# Flight_control_computer.net
KiCad netlist of a schematic drawn in EasyEDA
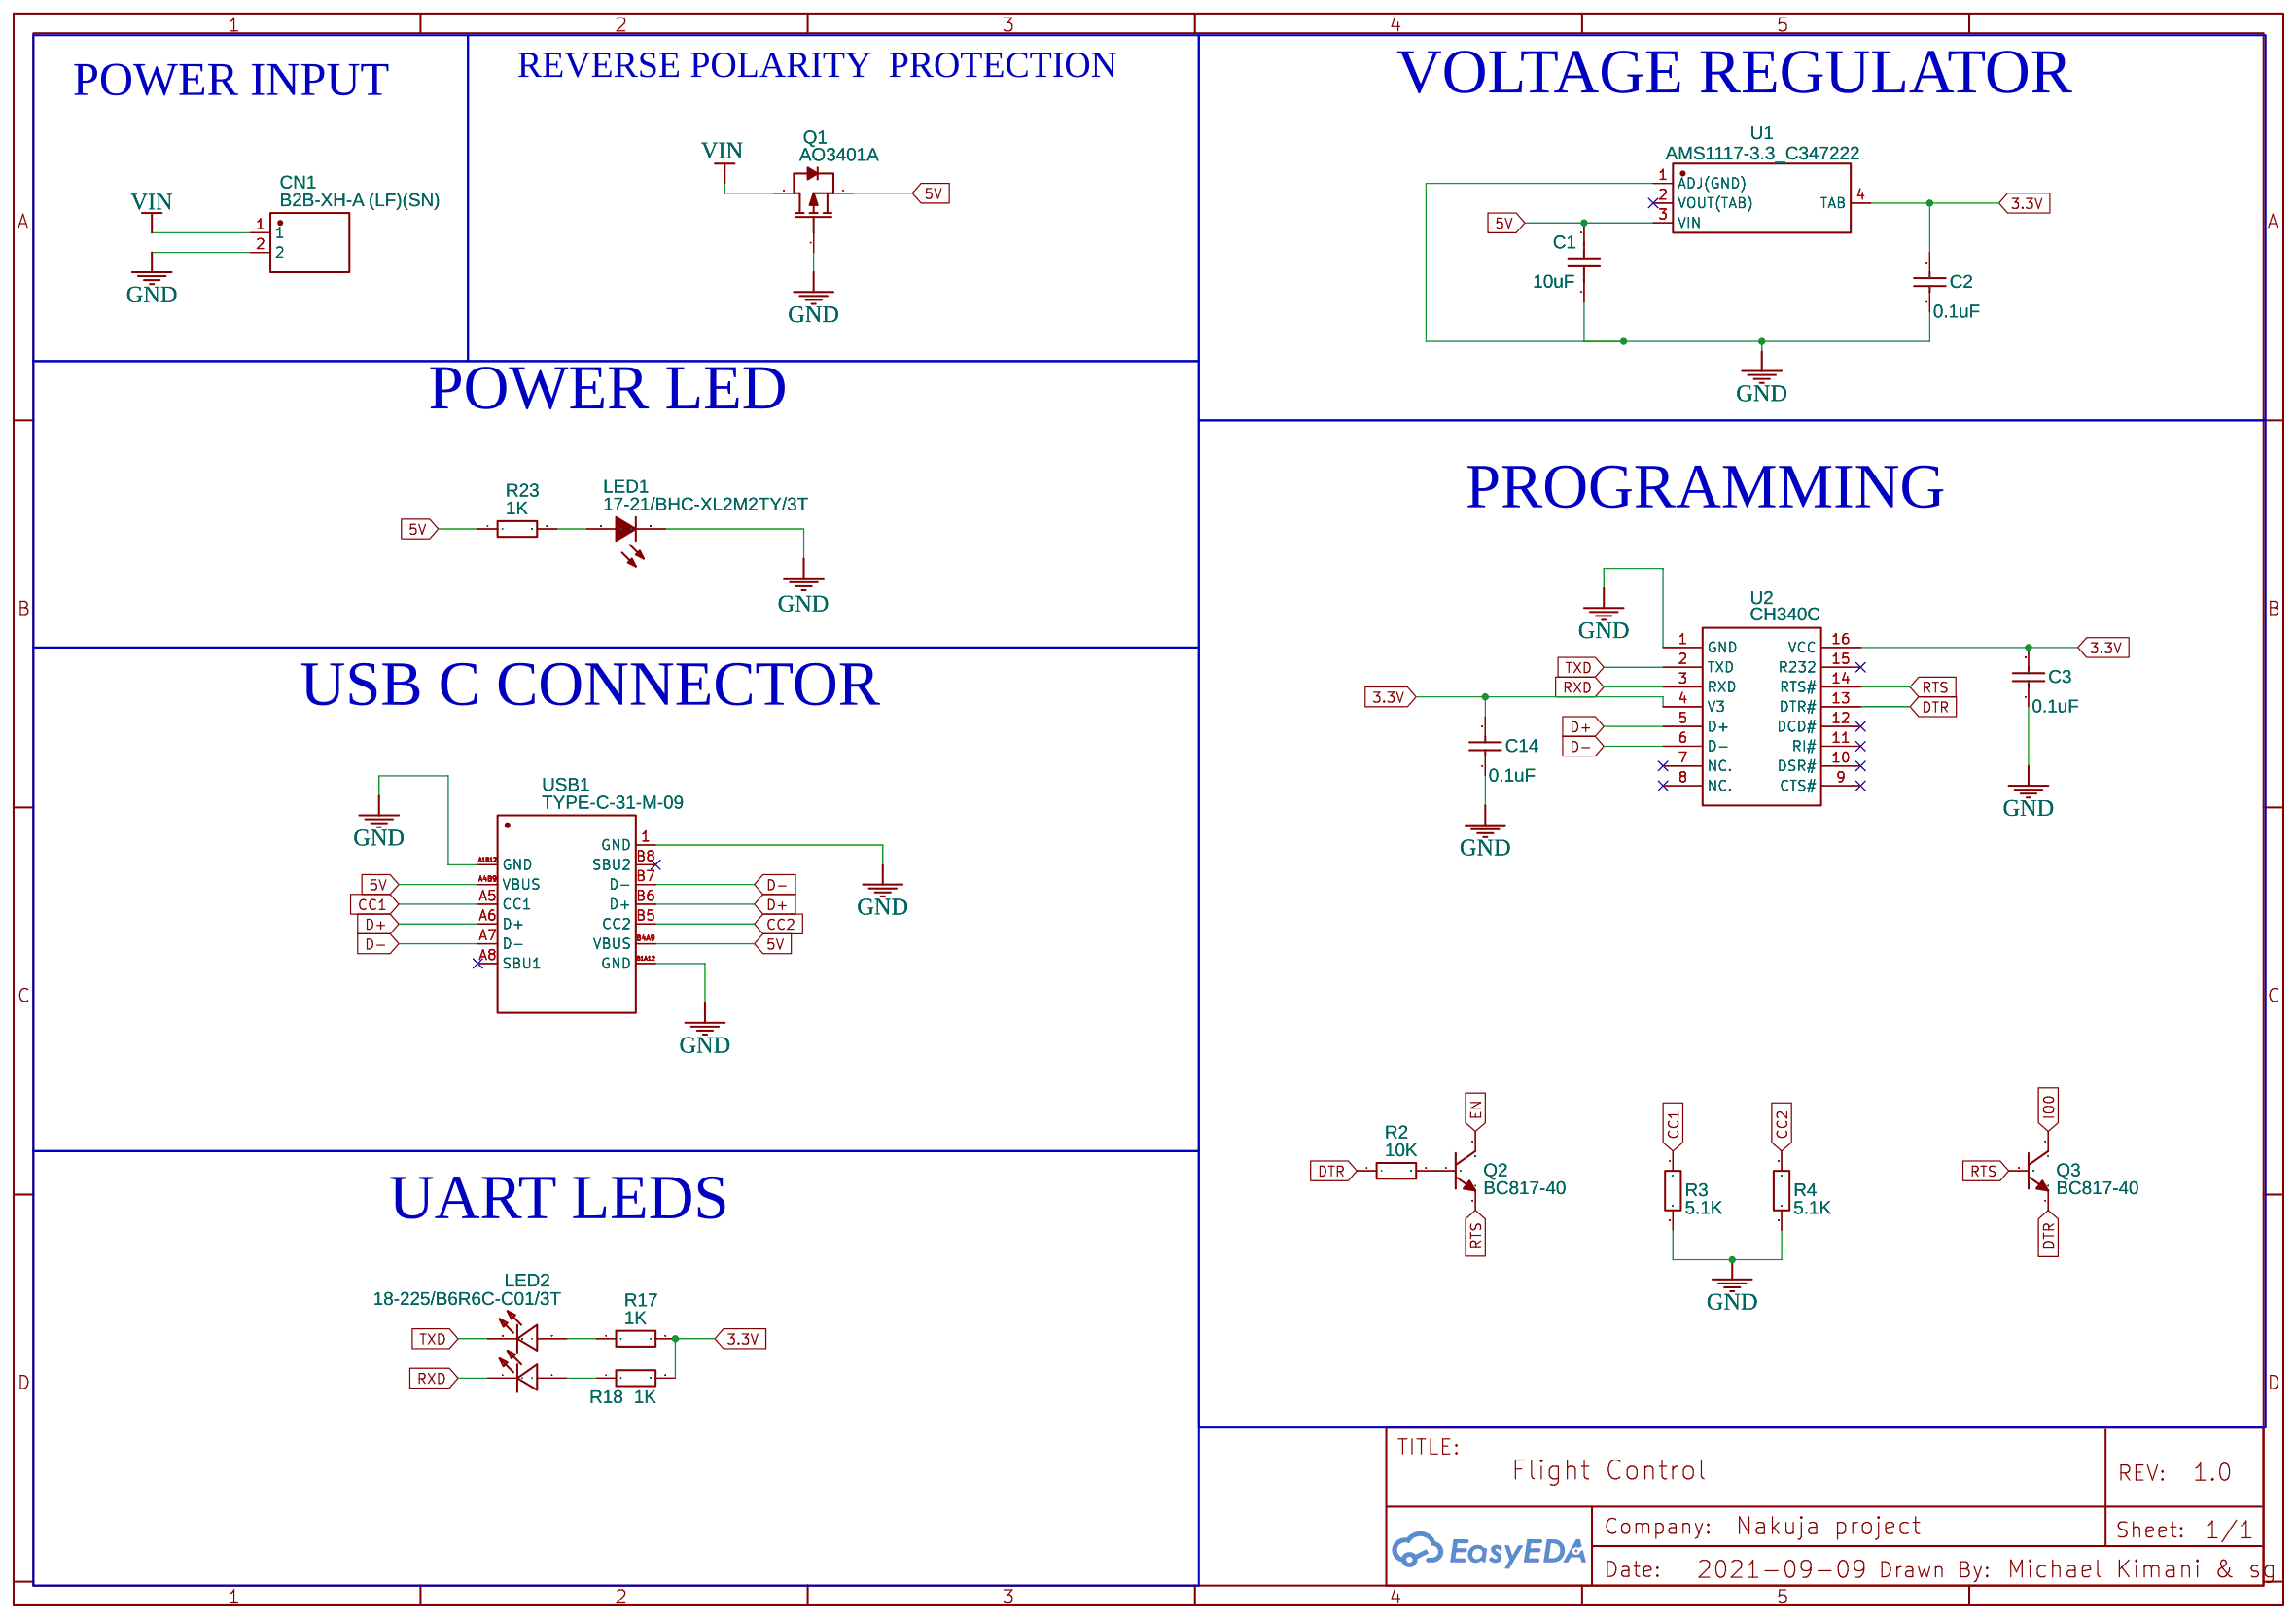
[diagram p0: power and programming]
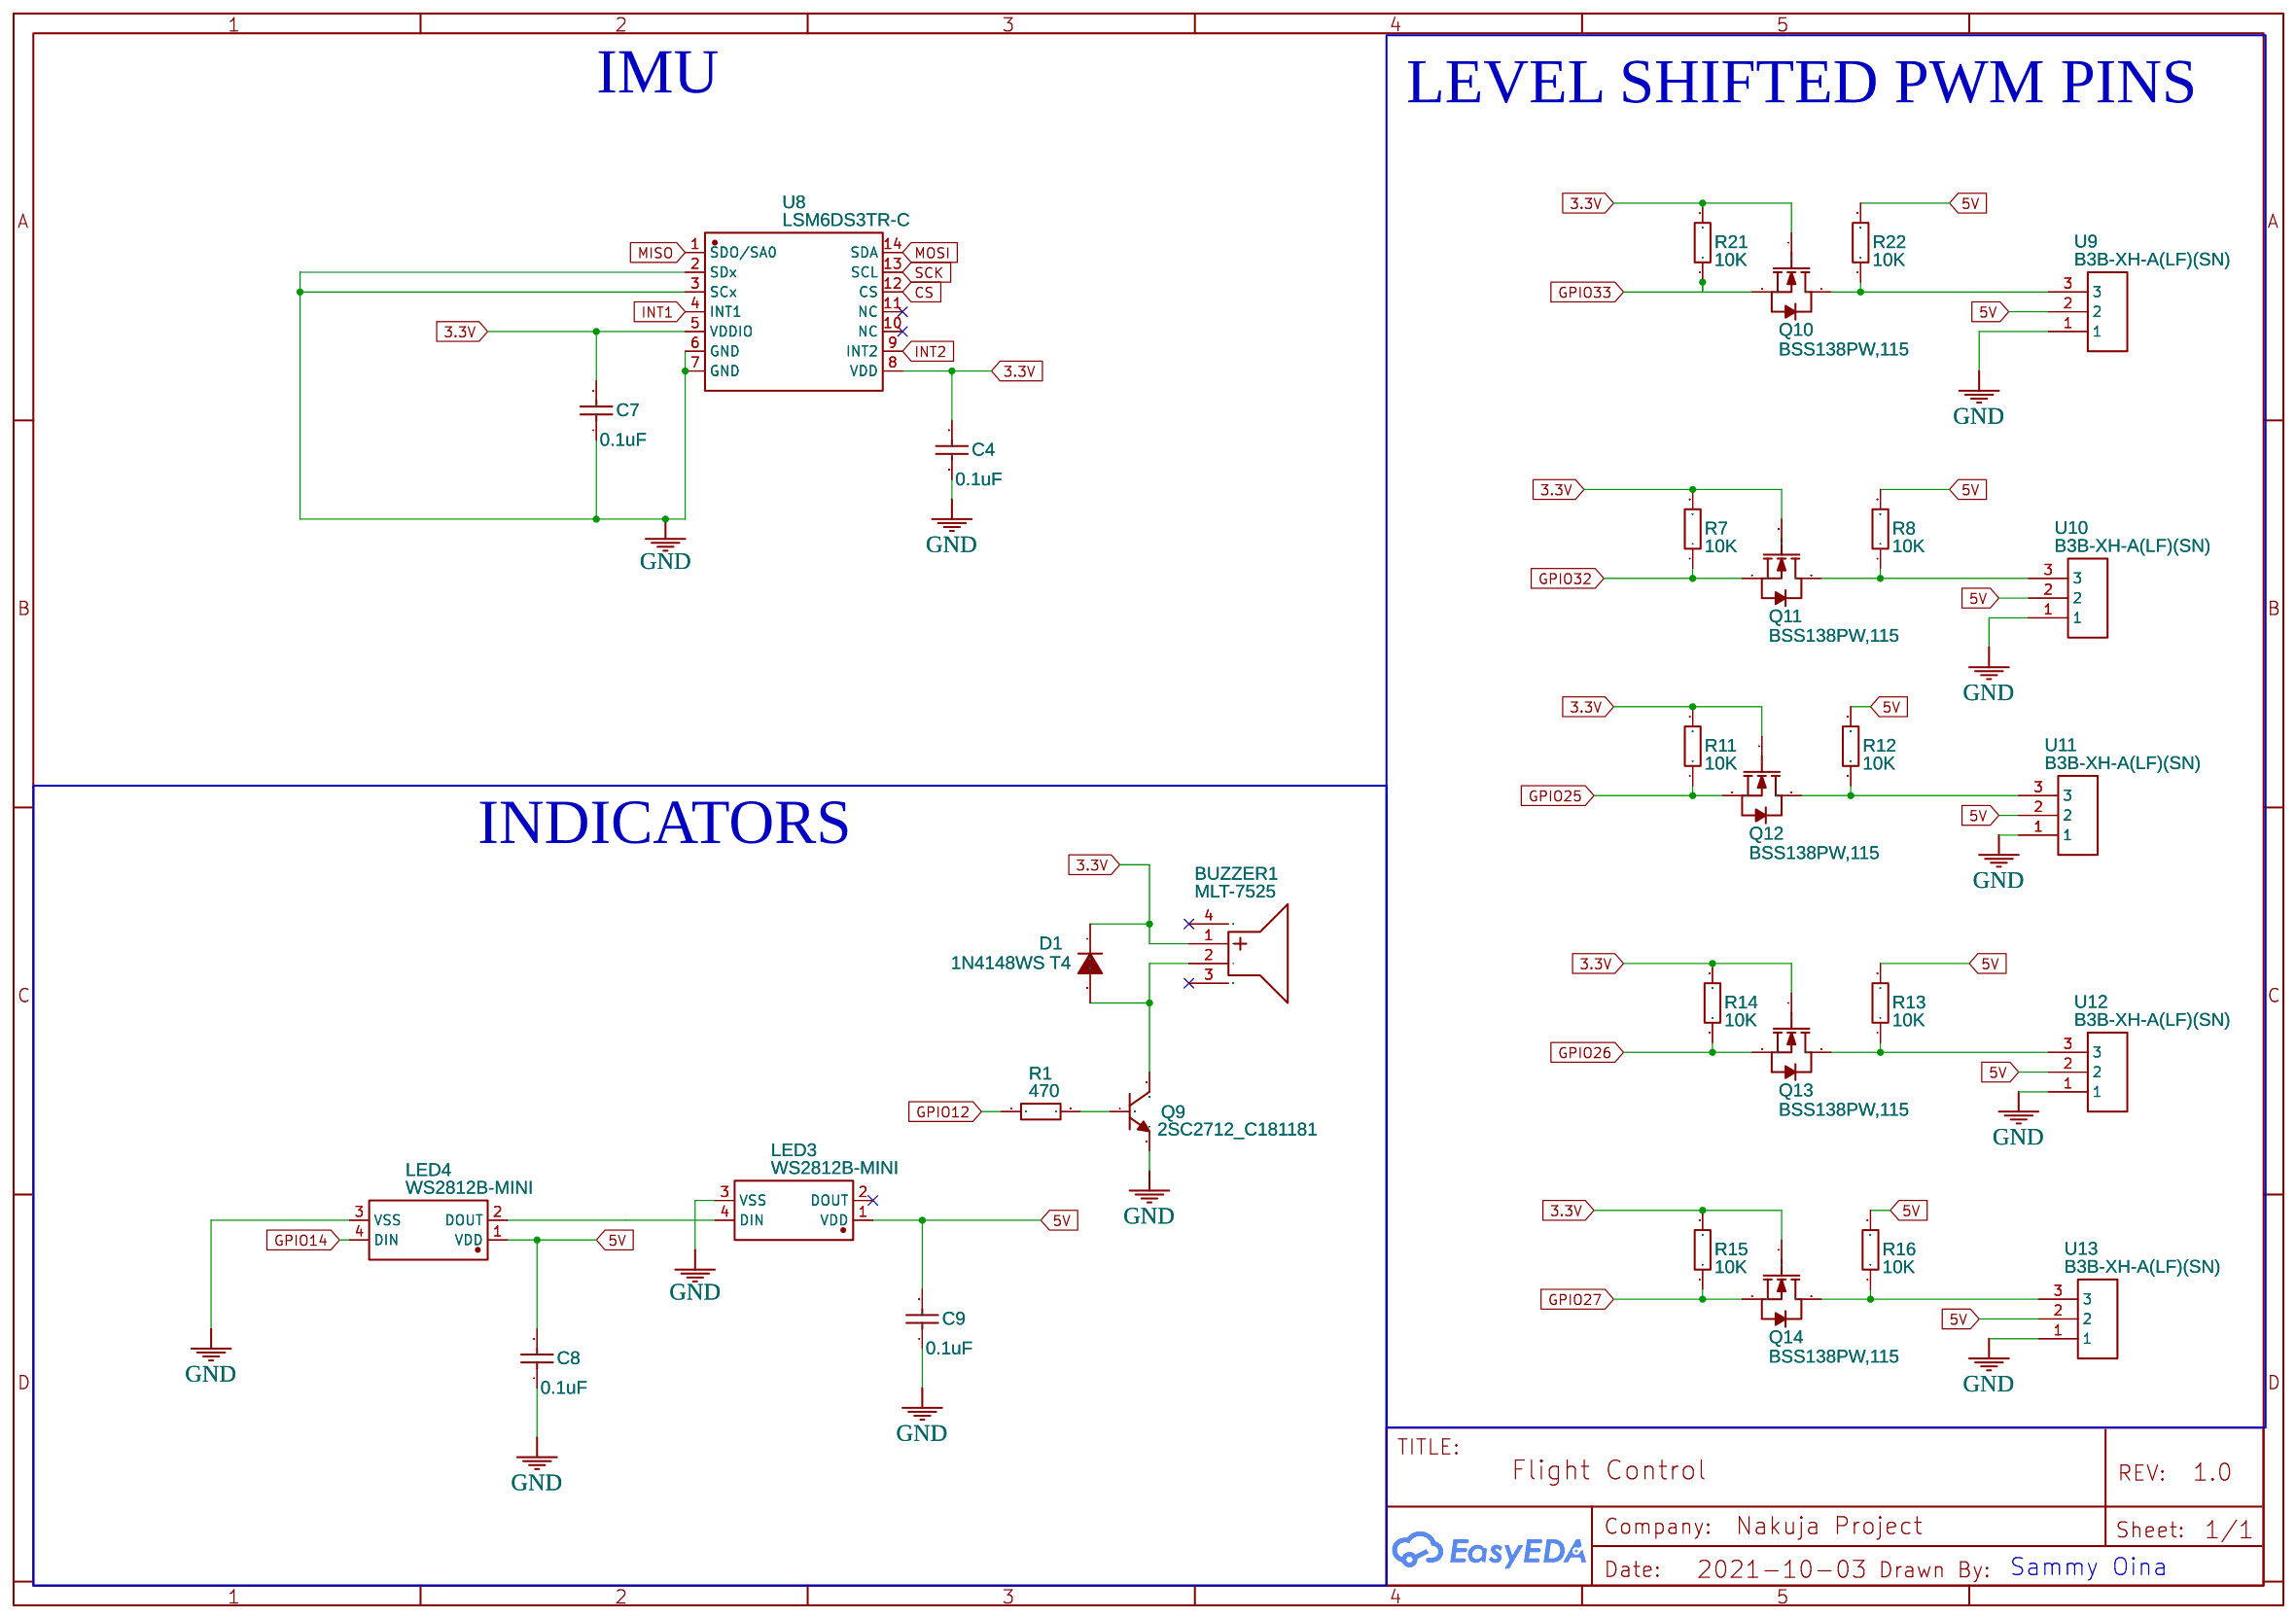
[diagram p1: indicators imu and pwmpins]
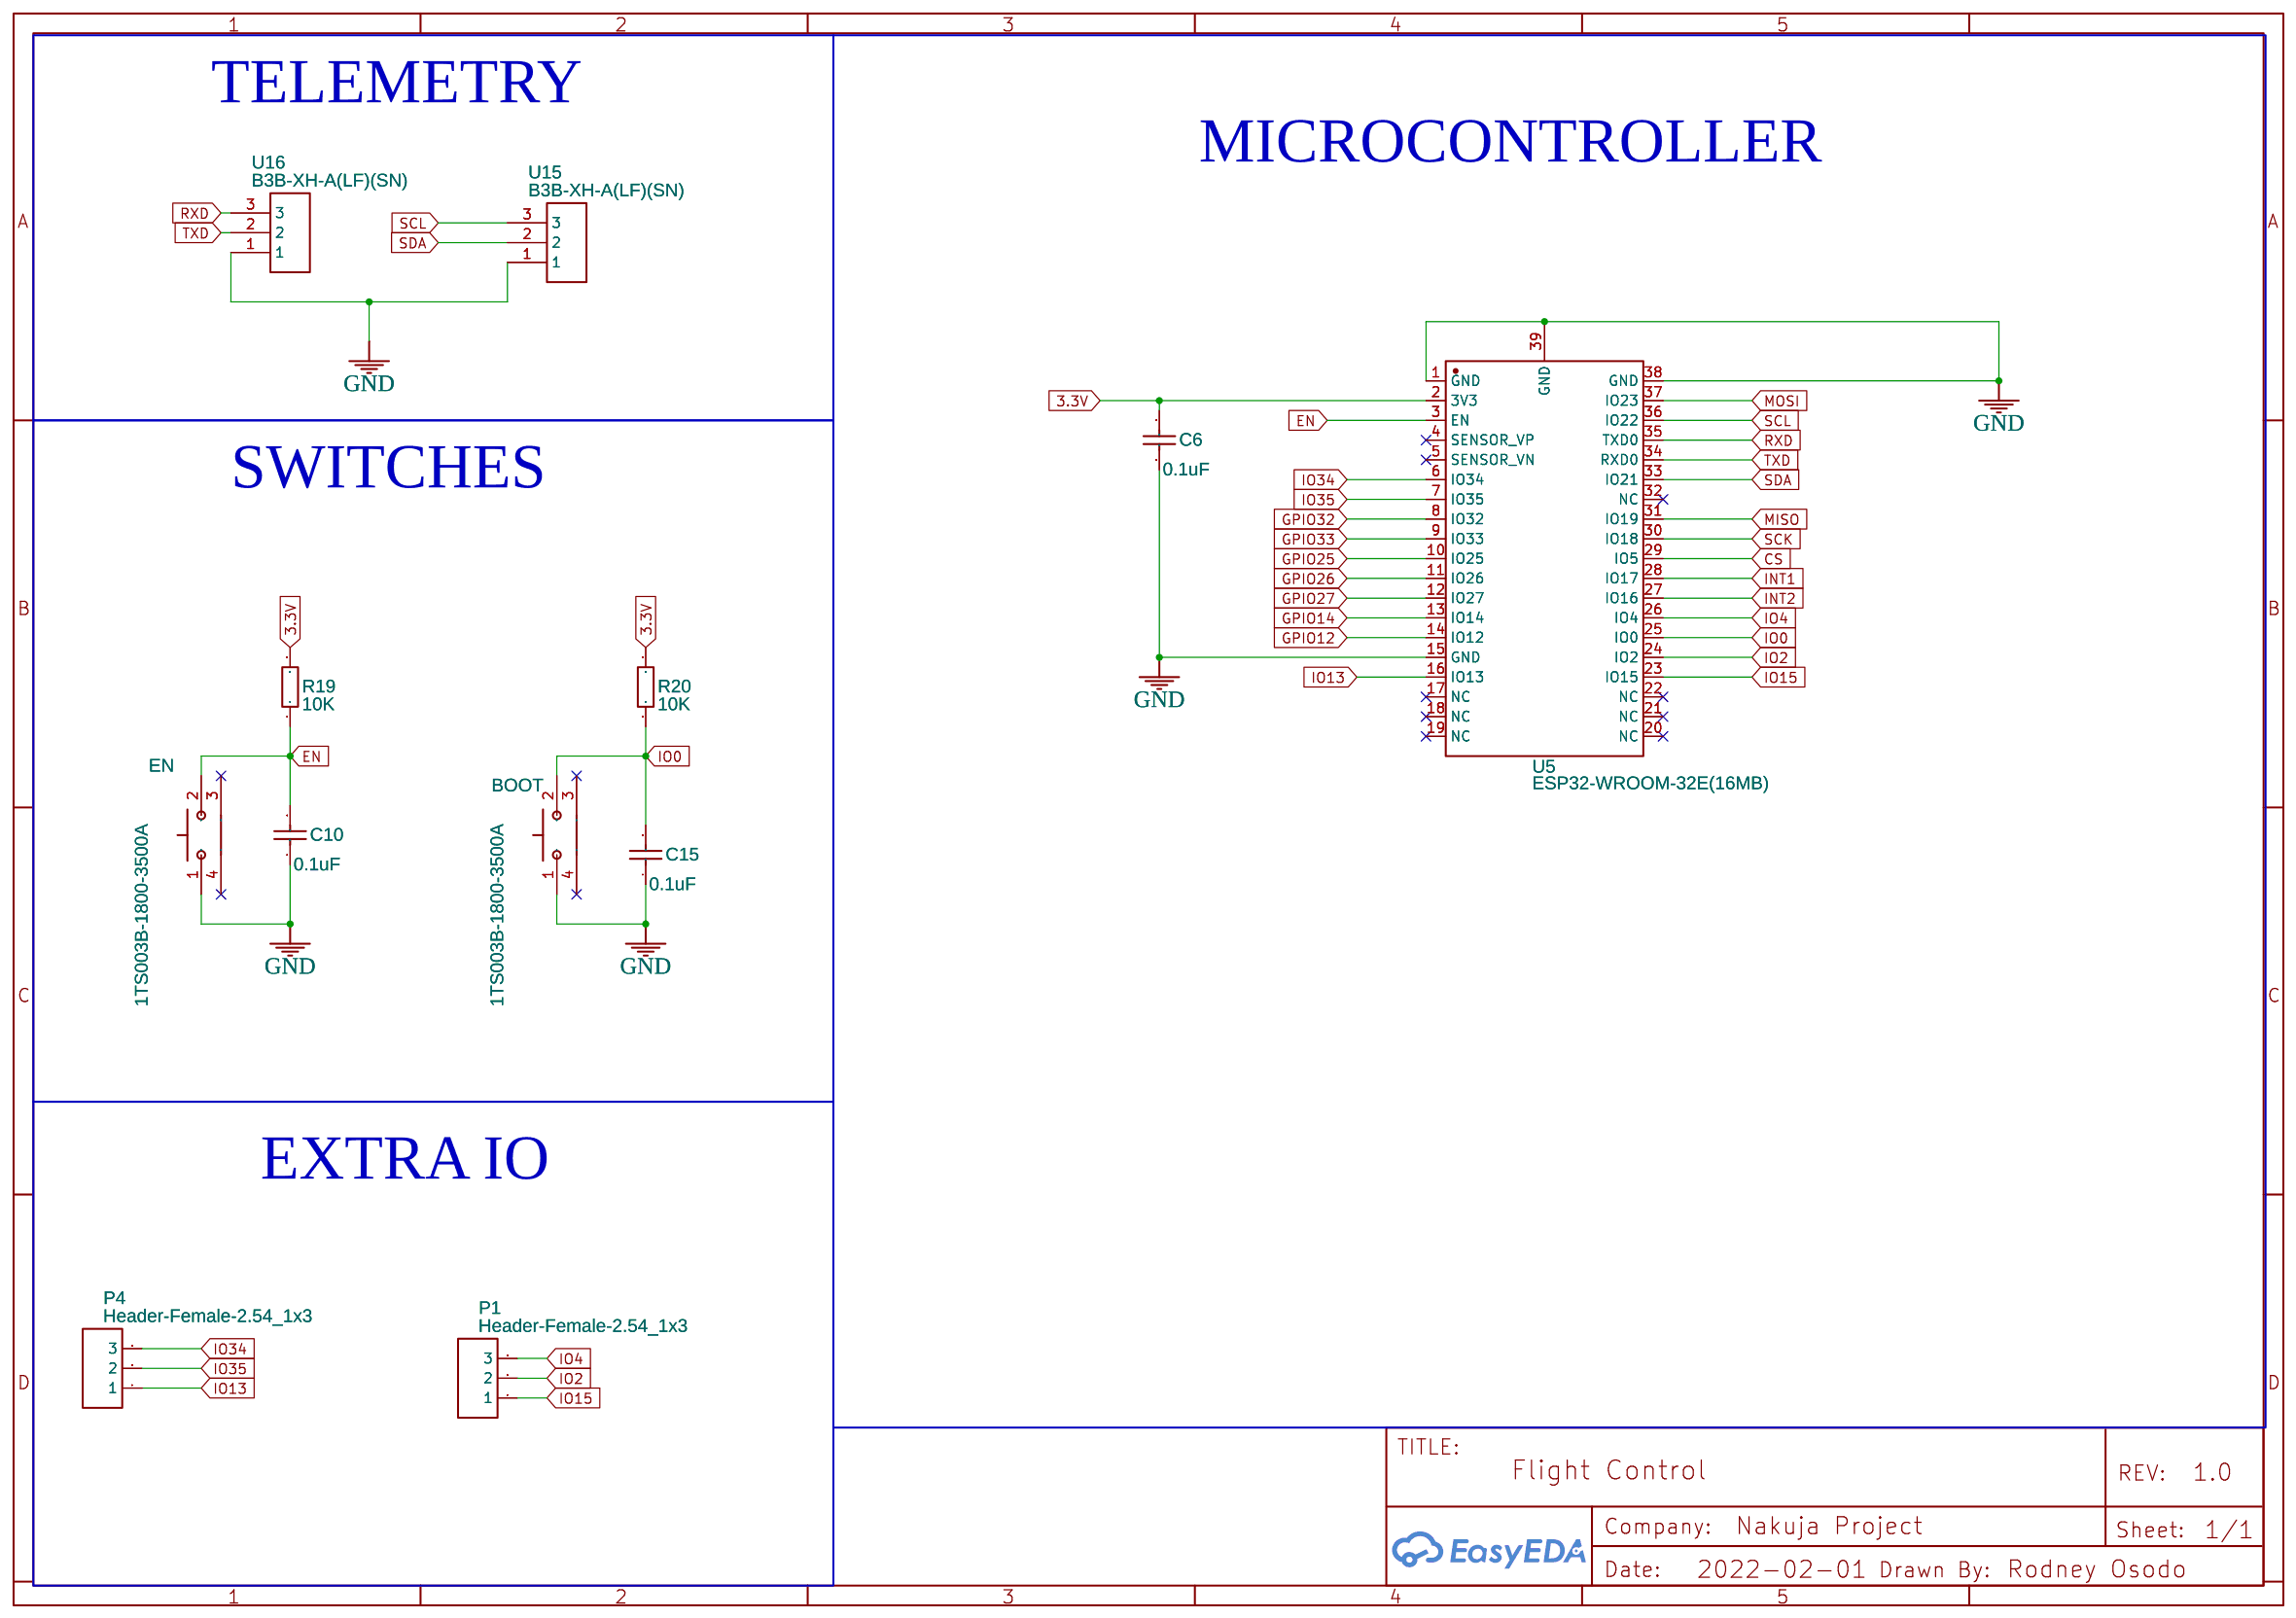
[diagram p2: microcontroller]

(export (version "E")
  (design (tool "Eeschema 10.0.6"))
  (components
    (comp (ref "C1")
      (value "10uF")
      (fields
        (field (name "BOM_Manufacturer Part") "CL05A106MQ8NUB8")
        (field (name "BOM_Supplier Part") "C307416")
      )
      (libsource (lib "") (part "CL05A106MQ8NUB8"))
    )
    (comp (ref "C2")
      (value "0.1uF")
      (fields
        (field (name "BOM_Manufacturer Part") "0603B104K250")
        (field (name "BOM_Supplier Part") "C83054")
      )
      (libsource (lib "") (part "0603B104K250"))
    )
    (comp (ref "C3")
      (value "0.1uF")
      (fields
        (field (name "BOM_Manufacturer Part") "0603B104K250")
        (field (name "BOM_Supplier Part") "C83054")
      )
      (libsource (lib "") (part "0603B104K250"))
    )
    (comp (ref "C14")
      (value "0.1uF")
      (fields
        (field (name "BOM_Manufacturer Part") "0603B104K250")
        (field (name "BOM_Supplier Part") "C83054")
      )
      (libsource (lib "") (part "0603B104K250"))
    )
    (comp (ref "CN1")
      (value "B2B-XH-A (LF)(SN)")
      (fields (field (name "BOM_Supplier Part") "C158012"))
      (libsource (lib "") (part "B2B-XH-A (LF)(SN)"))
    )
    (comp (ref "LED1")
      (value "17-21/BHC-XL2M2TY/3T")
      (fields (field (name "BOM_Supplier Part") "C72035"))
      (libsource (lib "") (part "17-21/BHC-XL2M2TY/3T"))
    )
    (comp (ref "LED2")
      (value "18-225/B6R6C-C01/3T")
      (fields (field (name "BOM_Supplier Part") "C282127"))
      (libsource (lib "") (part "18-225/B6R6C-C01/3T"))
    )
    (comp (ref "Q1")
      (value "AO3401A")
      (fields (field (name "BOM_Supplier Part") "C15127"))
      (libsource (lib "") (part "AO3401A"))
    )
    (comp (ref "Q2")
      (value "BC817-40")
      (fields (field (name "BOM_Supplier Part") "C181151"))
      (libsource (lib "") (part "BC817-40"))
    )
    (comp (ref "Q3")
      (value "BC817-40")
      (fields (field (name "BOM_Supplier Part") "C181151"))
      (libsource (lib "") (part "BC817-40"))
    )
    (comp (ref "R2")
      (value "10K")
      (fields
        (field (name "BOM_Manufacturer Part") "0402WGJ0103TCE")
        (field (name "BOM_Supplier Part") "C25531")
      )
      (libsource (lib "") (part "0402WGJ0103TCE"))
    )
    (comp (ref "R3")
      (value "5.1K")
      (fields
        (field (name "BOM_Manufacturer Part") "0402WGF5101TCE")
        (field (name "BOM_Supplier Part") "C25905")
      )
      (libsource (lib "") (part "0402WGF5101TCE"))
    )
    (comp (ref "R4")
      (value "5.1K")
      (fields
        (field (name "BOM_Manufacturer Part") "0402WGF5101TCE")
        (field (name "BOM_Supplier Part") "C25905")
      )
      (libsource (lib "") (part "0402WGF5101TCE"))
    )
    (comp (ref "R17")
      (value "1K")
      (fields
        (field (name "BOM_Manufacturer Part") "PTFR0805B1K00N9")
        (field (name "BOM_Supplier Part") "C328437")
      )
      (libsource (lib "") (part "PTFR0805B1K00N9"))
    )
    (comp (ref "R18")
      (value "1K")
      (fields
        (field (name "BOM_Manufacturer Part") "PTFR0805B1K00N9")
        (field (name "BOM_Supplier Part") "C328437")
      )
      (libsource (lib "") (part "PTFR0805B1K00N9"))
    )
    (comp (ref "R23")
      (value "1K")
      (fields
        (field (name "BOM_Manufacturer Part") "PTFR0805B1K00N9")
        (field (name "BOM_Supplier Part") "C328437")
      )
      (libsource (lib "") (part "PTFR0805B1K00N9"))
    )
    (comp (ref "U1")
      (value "AMS1117-3.3_C347222")
      (fields
        (field (name "BOM_Manufacturer Part") "AMS1117-3.3")
        (field (name "BOM_Supplier Part") "C347222")
      )
      (libsource (lib "") (part "AMS1117-3.3_C347222"))
    )
    (comp (ref "U2")
      (value "CH340C")
      (fields (field (name "BOM_Supplier Part") "C84681"))
      (libsource (lib "") (part "CH340C"))
    )
    (comp (ref "USB1")
      (value "TYPE-C-31-M-09")
      (fields (field (name "BOM_Supplier Part") "C2689967"))
      (libsource (lib "") (part "TYPE-C-31-M-09"))
    )
    (comp (ref "BUZZER1")
      (value "MLT-7525")
      (fields (field (name "BOM_Supplier Part") "C95299"))
      (libsource (lib "") (part "MLT-7525"))
    )
    (comp (ref "C4")
      (value "0.1uF")
      (fields
        (field (name "BOM_Manufacturer Part") "0603B104K250")
        (field (name "BOM_Supplier Part") "C83054")
      )
      (libsource (lib "") (part "0603B104K250"))
    )
    (comp (ref "C7")
      (value "0.1uF")
      (fields
        (field (name "BOM_Manufacturer Part") "0603B104K250")
        (field (name "BOM_Supplier Part") "C83054")
      )
      (libsource (lib "") (part "0603B104K250"))
    )
    (comp (ref "C8")
      (value "0.1uF")
      (fields
        (field (name "BOM_Manufacturer Part") "0603B104K250")
        (field (name "BOM_Supplier Part") "C83054")
      )
      (libsource (lib "") (part "0603B104K250"))
    )
    (comp (ref "C9")
      (value "0.1uF")
      (fields
        (field (name "BOM_Manufacturer Part") "0603B104K250")
        (field (name "BOM_Supplier Part") "C83054")
      )
      (libsource (lib "") (part "0603B104K250"))
    )
    (comp (ref "D1")
      (value "1N4148WS T4")
      (fields (field (name "BOM_Supplier Part") "C2128"))
      (libsource (lib "") (part "1N4148WS T4"))
    )
    (comp (ref "LED3")
      (value "WS2812B-MINI")
      (fields
        (field (name "BOM_Manufacturer Part") "WS2812B-Mini")
        (field (name "BOM_Supplier Part") "C527089")
      )
      (libsource (lib "") (part "WS2812B-MINI"))
    )
    (comp (ref "LED4")
      (value "WS2812B-MINI")
      (fields
        (field (name "BOM_Manufacturer Part") "WS2812B-Mini")
        (field (name "BOM_Supplier Part") "C527089")
      )
      (libsource (lib "") (part "WS2812B-MINI"))
    )
    (comp (ref "Q9")
      (value "2SC2712_C181181")
      (fields (field (name "BOM_Manufacturer Part") "2SC2712") (field (name "BOM_Supplier Part") "C181181"))
      (libsource (lib "") (part "2SC2712_C181181"))
    )
    (comp (ref "Q10")
      (value "BSS138PW,115")
      (fields (field (name "BOM_Supplier Part") "C193366"))
      (libsource (lib "") (part "BSS138PW,115"))
    )
    (comp (ref "Q11")
      (value "BSS138PW,115")
      (fields (field (name "BOM_Supplier Part") "C193366"))
      (libsource (lib "") (part "BSS138PW,115"))
    )
    (comp (ref "Q12")
      (value "BSS138PW,115")
      (fields (field (name "BOM_Supplier Part") "C193366"))
      (libsource (lib "") (part "BSS138PW,115"))
    )
    (comp (ref "Q13")
      (value "BSS138PW,115")
      (fields (field (name "BOM_Supplier Part") "C193366"))
      (libsource (lib "") (part "BSS138PW,115"))
    )
    (comp (ref "Q14")
      (value "BSS138PW,115")
      (fields (field (name "BOM_Supplier Part") "C193366"))
      (libsource (lib "") (part "BSS138PW,115"))
    )
    (comp (ref "R1")
      (value "470")
      (fields
        (field (name "BOM_Manufacturer Part") "0805W8F4700T5E")
        (field (name "BOM_Supplier Part") "C17710")
      )
      (libsource (lib "") (part "0805W8F4700T5E"))
    )
    (comp (ref "R7")
      (value "10K")
      (fields
        (field (name "BOM_Manufacturer Part") "0402WGJ0103TCE")
        (field (name "BOM_Supplier Part") "C25531")
      )
      (libsource (lib "") (part "0402WGJ0103TCE"))
    )
    (comp (ref "R8")
      (value "10K")
      (fields
        (field (name "BOM_Manufacturer Part") "0402WGJ0103TCE")
        (field (name "BOM_Supplier Part") "C25531")
      )
      (libsource (lib "") (part "0402WGJ0103TCE"))
    )
    (comp (ref "R11")
      (value "10K")
      (fields
        (field (name "BOM_Manufacturer Part") "0402WGJ0103TCE")
        (field (name "BOM_Supplier Part") "C25531")
      )
      (libsource (lib "") (part "0402WGJ0103TCE"))
    )
    (comp (ref "R12")
      (value "10K")
      (fields
        (field (name "BOM_Manufacturer Part") "0402WGJ0103TCE")
        (field (name "BOM_Supplier Part") "C25531")
      )
      (libsource (lib "") (part "0402WGJ0103TCE"))
    )
    (comp (ref "R13")
      (value "10K")
      (fields
        (field (name "BOM_Manufacturer Part") "0402WGJ0103TCE")
        (field (name "BOM_Supplier Part") "C25531")
      )
      (libsource (lib "") (part "0402WGJ0103TCE"))
    )
    (comp (ref "R14")
      (value "10K")
      (fields
        (field (name "BOM_Manufacturer Part") "0402WGJ0103TCE")
        (field (name "BOM_Supplier Part") "C25531")
      )
      (libsource (lib "") (part "0402WGJ0103TCE"))
    )
    (comp (ref "R15")
      (value "10K")
      (fields
        (field (name "BOM_Manufacturer Part") "0402WGJ0103TCE")
        (field (name "BOM_Supplier Part") "C25531")
      )
      (libsource (lib "") (part "0402WGJ0103TCE"))
    )
    (comp (ref "R16")
      (value "10K")
      (fields
        (field (name "BOM_Manufacturer Part") "0402WGJ0103TCE")
        (field (name "BOM_Supplier Part") "C25531")
      )
      (libsource (lib "") (part "0402WGJ0103TCE"))
    )
    (comp (ref "R21")
      (value "10K")
      (fields
        (field (name "BOM_Manufacturer Part") "0402WGJ0103TCE")
        (field (name "BOM_Supplier Part") "C25531")
      )
      (libsource (lib "") (part "0402WGJ0103TCE"))
    )
    (comp (ref "R22")
      (value "10K")
      (fields
        (field (name "BOM_Manufacturer Part") "0402WGJ0103TCE")
        (field (name "BOM_Supplier Part") "C25531")
      )
      (libsource (lib "") (part "0402WGJ0103TCE"))
    )
    (comp (ref "U8")
      (value "LSM6DS3TR-C")
      (fields (field (name "BOM_Supplier Part") "C967633"))
      (libsource (lib "") (part "LSM6DS3TR-C"))
    )
    (comp (ref "U9")
      (value "B3B-XH-A(LF)(SN)")
      (fields (field (name "BOM_Supplier Part") "C144394"))
      (libsource (lib "") (part "B3B-XH-A(LF)(SN)"))
    )
    (comp (ref "U10")
      (value "B3B-XH-A(LF)(SN)")
      (fields (field (name "BOM_Supplier Part") "C144394"))
      (libsource (lib "") (part "B3B-XH-A(LF)(SN)"))
    )
    (comp (ref "U11")
      (value "B3B-XH-A(LF)(SN)")
      (fields (field (name "BOM_Supplier Part") "C144394"))
      (libsource (lib "") (part "B3B-XH-A(LF)(SN)"))
    )
    (comp (ref "U12")
      (value "B3B-XH-A(LF)(SN)")
      (fields (field (name "BOM_Supplier Part") "C144394"))
      (libsource (lib "") (part "B3B-XH-A(LF)(SN)"))
    )
    (comp (ref "U13")
      (value "B3B-XH-A(LF)(SN)")
      (fields (field (name "BOM_Supplier Part") "C144394"))
      (libsource (lib "") (part "B3B-XH-A(LF)(SN)"))
    )
    (comp (ref "BOOT")
      (value "1TS003B-1800-3500A")
      (fields (field (name "BOM_Supplier Part") "C255809"))
      (libsource (lib "") (part "1TS003B-1800-3500A"))
    )
    (comp (ref "C6")
      (value "0.1uF")
      (fields
        (field (name "BOM_Manufacturer Part") "0603B104K250")
        (field (name "BOM_Supplier Part") "C83054")
      )
      (libsource (lib "") (part "0603B104K250"))
    )
    (comp (ref "C10")
      (value "0.1uF")
      (fields
        (field (name "BOM_Manufacturer Part") "0603B104K250")
        (field (name "BOM_Supplier Part") "C83054")
      )
      (libsource (lib "") (part "0603B104K250"))
    )
    (comp (ref "C15")
      (value "0.1uF")
      (fields
        (field (name "BOM_Manufacturer Part") "0603B104K250")
        (field (name "BOM_Supplier Part") "C83054")
      )
      (libsource (lib "") (part "0603B104K250"))
    )
    (comp (ref "EN")
      (value "1TS003B-1800-3500A")
      (fields (field (name "BOM_Supplier Part") "C255809"))
      (libsource (lib "") (part "1TS003B-1800-3500A_1"))
    )
    (comp (ref "P1")
      (value "Header-Female-2.54_1x3")
      (fields (field (name "BOM_Supplier Part") "C146243"))
      (libsource (lib "") (part "Header-Female-2.54_1x3"))
    )
    (comp (ref "P4")
      (value "Header-Female-2.54_1x3")
      (fields (field (name "BOM_Supplier Part") "C146243"))
      (libsource (lib "") (part "Header-Female-2.54_1x3"))
    )
    (comp (ref "R19")
      (value "10K")
      (fields
        (field (name "BOM_Manufacturer Part") "0402WGJ0103TCE")
        (field (name "BOM_Supplier Part") "C25531")
      )
      (libsource (lib "") (part "0402WGJ0103TCE"))
    )
    (comp (ref "R20")
      (value "10K")
      (fields
        (field (name "BOM_Manufacturer Part") "0402WGJ0103TCE")
        (field (name "BOM_Supplier Part") "C25531")
      )
      (libsource (lib "") (part "0402WGJ0103TCE"))
    )
    (comp (ref "U5")
      (value "ESP32-WROOM-32E(16MB)")
      (fields (field (name "BOM_Supplier Part") "C701343"))
      (libsource (lib "") (part "ESP32-WROOM-32E(16MB)"))
    )
    (comp (ref "U15")
      (value "B3B-XH-A(LF)(SN)")
      (fields (field (name "BOM_Supplier Part") "C144394"))
      (libsource (lib "") (part "B3B-XH-A(LF)(SN)"))
    )
    (comp (ref "U16")
      (value "B3B-XH-A(LF)(SN)")
      (fields (field (name "BOM_Supplier Part") "C144394"))
      (libsource (lib "") (part "B3B-XH-A(LF)(SN)"))
    )
  )
  (nets
    (net (code "1") (name "3.3V") (class "Default")
      (node (ref "BUZZER1") (pin "1") (pinfunction "+_1") (pintype "unspecified"))
      (node (ref "C14") (pin "2") (pinfunction "2_2") (pintype "input"))
      (node (ref "C2") (pin "2") (pinfunction "2_2") (pintype "input"))
      (node (ref "C3") (pin "2") (pinfunction "2_2") (pintype "input"))
      (node (ref "C4") (pin "2") (pinfunction "2_2") (pintype "input"))
      (node (ref "C6") (pin "2") (pinfunction "2_2") (pintype "input"))
      (node (ref "C7") (pin "2") (pinfunction "2_2") (pintype "input"))
      (node (ref "D1") (pin "1") (pinfunction "K_1") (pintype "unspecified"))
      (node (ref "Q10") (pin "1") (pinfunction "G_1") (pintype "unspecified"))
      (node (ref "Q11") (pin "1") (pinfunction "G_1") (pintype "unspecified"))
      (node (ref "Q12") (pin "1") (pinfunction "G_1") (pintype "unspecified"))
      (node (ref "Q13") (pin "1") (pinfunction "G_1") (pintype "unspecified"))
      (node (ref "Q14") (pin "1") (pinfunction "G_1") (pintype "unspecified"))
      (node (ref "R11") (pin "2") (pinfunction "2_2") (pintype "input"))
      (node (ref "R14") (pin "2") (pinfunction "2_2") (pintype "input"))
      (node (ref "R15") (pin "2") (pinfunction "2_2") (pintype "input"))
      (node (ref "R17") (pin "2") (pinfunction "2_2") (pintype "unspecified"))
      (node (ref "R18") (pin "2") (pinfunction "2_2") (pintype "unspecified"))
      (node (ref "R19") (pin "2") (pinfunction "2_2") (pintype "input"))
      (node (ref "R20") (pin "2") (pinfunction "2_2") (pintype "input"))
      (node (ref "R21") (pin "2") (pinfunction "2_2") (pintype "input"))
      (node (ref "R7") (pin "2") (pinfunction "2_2") (pintype "input"))
      (node (ref "U1") (pin "4") (pinfunction "TAB_4") (pintype "unspecified"))
      (node (ref "U2") (pin "16") (pinfunction "VCC_16") (pintype "unspecified"))
      (node (ref "U2") (pin "4") (pinfunction "V3_4") (pintype "unspecified"))
      (node (ref "U5") (pin "2") (pinfunction "3V3_2") (pintype "unspecified"))
      (node (ref "U8") (pin "5") (pinfunction "VDDIO_5") (pintype "unspecified"))
      (node (ref "U8") (pin "8") (pinfunction "VDD_8") (pintype "unspecified"))
    )
    (net (code "2") (name "5V") (class "Default")
      (node (ref "C1") (pin "2") (pinfunction "2_2") (pintype "unspecified"))
      (node (ref "C8") (pin "2") (pinfunction "2_2") (pintype "input"))
      (node (ref "C9") (pin "2") (pinfunction "2_2") (pintype "input"))
      (node (ref "LED3") (pin "1") (pinfunction "VDD_1") (pintype "unspecified"))
      (node (ref "LED4") (pin "1") (pinfunction "VDD_1") (pintype "unspecified"))
      (node (ref "Q1") (pin "2") (pinfunction "S_2") (pintype "unspecified"))
      (node (ref "R12") (pin "2") (pinfunction "2_2") (pintype "input"))
      (node (ref "R13") (pin "2") (pinfunction "2_2") (pintype "input"))
      (node (ref "R16") (pin "2") (pinfunction "2_2") (pintype "input"))
      (node (ref "R22") (pin "2") (pinfunction "2_2") (pintype "input"))
      (node (ref "R23") (pin "1") (pinfunction "1_1") (pintype "unspecified"))
      (node (ref "R8") (pin "2") (pinfunction "2_2") (pintype "input"))
      (node (ref "U1") (pin "3") (pinfunction "VIN_3") (pintype "unspecified"))
      (node (ref "U10") (pin "2") (pinfunction "2_2") (pintype "unspecified"))
      (node (ref "U11") (pin "2") (pinfunction "2_2") (pintype "unspecified"))
      (node (ref "U12") (pin "2") (pinfunction "2_2") (pintype "unspecified"))
      (node (ref "U13") (pin "2") (pinfunction "2_2") (pintype "unspecified"))
      (node (ref "U9") (pin "2") (pinfunction "2_2") (pintype "unspecified"))
      (node (ref "USB1") (pin "A4B9") (pinfunction "VBUS_A4B9") (pintype "unspecified"))
      (node (ref "USB1") (pin "B4A9") (pinfunction "VBUS_B4A9") (pintype "unspecified"))
    )
    (net (code "3") (name "CC1") (class "Default")
      (node (ref "R3") (pin "1") (pinfunction "1_1") (pintype "input"))
      (node (ref "USB1") (pin "A5") (pinfunction "CC1_A5") (pintype "unspecified"))
    )
    (net (code "4") (name "CC2") (class "Default")
      (node (ref "R4") (pin "1") (pinfunction "1_1") (pintype "input"))
      (node (ref "USB1") (pin "B5") (pinfunction "CC2_B5") (pintype "unspecified"))
    )
    (net (code "5") (name "CS") (class "Default")
      (node (ref "U5") (pin "29") (pinfunction "IO5_29") (pintype "unspecified"))
      (node (ref "U8") (pin "12") (pinfunction "CS_12") (pintype "unspecified"))
    )
    (net (code "6") (name "D+") (class "Default")
      (node (ref "U2") (pin "5") (pinfunction "D+_5") (pintype "unspecified"))
      (node (ref "USB1") (pin "A6") (pinfunction "D+_A6") (pintype "unspecified"))
      (node (ref "USB1") (pin "B6") (pinfunction "D+_B6") (pintype "unspecified"))
    )
    (net (code "7") (name "D-") (class "Default")
      (node (ref "U2") (pin "6") (pinfunction "D-_6") (pintype "unspecified"))
      (node (ref "USB1") (pin "A7") (pinfunction "D-_A7") (pintype "unspecified"))
      (node (ref "USB1") (pin "B7") (pinfunction "D-_B7") (pintype "unspecified"))
    )
    (net (code "8") (name "DTR") (class "Default")
      (node (ref "Q3") (pin "2") (pinfunction "2_2") (pintype "input"))
      (node (ref "R2") (pin "1") (pinfunction "1_1") (pintype "input"))
      (node (ref "U2") (pin "13") (pinfunction "DTR#_13") (pintype "unspecified"))
    )
    (net (code "9") (name "EN") (class "Default")
      (node (ref "C10") (pin "2") (pinfunction "2_2") (pintype "input"))
      (node (ref "EN") (pin "2") (pinfunction "2_2") (pintype "unspecified"))
      (node (ref "Q2") (pin "3") (pinfunction "3_3") (pintype "input"))
      (node (ref "R19") (pin "1") (pinfunction "1_1") (pintype "input"))
      (node (ref "U5") (pin "3") (pinfunction "EN_3") (pintype "unspecified"))
    )
    (net (code "10") (name "GND") (class "Default")
      (node (ref "BOOT") (pin "1") (pinfunction "1_1") (pintype "unspecified"))
      (node (ref "C1") (pin "1") (pinfunction "1_1") (pintype "unspecified"))
      (node (ref "C10") (pin "1") (pinfunction "1_1") (pintype "input"))
      (node (ref "C14") (pin "1") (pinfunction "1_1") (pintype "input"))
      (node (ref "C15") (pin "1") (pinfunction "1_1") (pintype "input"))
      (node (ref "C2") (pin "1") (pinfunction "1_1") (pintype "input"))
      (node (ref "C3") (pin "1") (pinfunction "1_1") (pintype "input"))
      (node (ref "C4") (pin "1") (pinfunction "1_1") (pintype "input"))
      (node (ref "C6") (pin "1") (pinfunction "1_1") (pintype "input"))
      (node (ref "C7") (pin "1") (pinfunction "1_1") (pintype "input"))
      (node (ref "C8") (pin "1") (pinfunction "1_1") (pintype "input"))
      (node (ref "C9") (pin "1") (pinfunction "1_1") (pintype "input"))
      (node (ref "CN1") (pin "2") (pinfunction "2_2") (pintype "unspecified"))
      (node (ref "EN") (pin "1") (pinfunction "1_1") (pintype "unspecified"))
      (node (ref "LED1") (pin "1") (pinfunction "-_1") (pintype "input"))
      (node (ref "LED3") (pin "3") (pinfunction "VSS_3") (pintype "unspecified"))
      (node (ref "LED4") (pin "3") (pinfunction "VSS_3") (pintype "unspecified"))
      (node (ref "Q1") (pin "1") (pinfunction "G_1") (pintype "unspecified"))
      (node (ref "Q9") (pin "2") (pinfunction "E_2") (pintype "input"))
      (node (ref "R3") (pin "2") (pinfunction "2_2") (pintype "input"))
      (node (ref "R4") (pin "2") (pinfunction "2_2") (pintype "input"))
      (node (ref "U1") (pin "1") (pinfunction "ADJ(GND)_1") (pintype "unspecified"))
      (node (ref "U10") (pin "1") (pinfunction "1_1") (pintype "unspecified"))
      (node (ref "U11") (pin "1") (pinfunction "1_1") (pintype "unspecified"))
      (node (ref "U12") (pin "1") (pinfunction "1_1") (pintype "unspecified"))
      (node (ref "U13") (pin "1") (pinfunction "1_1") (pintype "unspecified"))
      (node (ref "U15") (pin "1") (pinfunction "1_1") (pintype "unspecified"))
      (node (ref "U16") (pin "1") (pinfunction "1_1") (pintype "unspecified"))
      (node (ref "U2") (pin "1") (pinfunction "GND_1") (pintype "unspecified"))
      (node (ref "U5") (pin "1") (pinfunction "GND_1") (pintype "unspecified"))
      (node (ref "U5") (pin "15") (pinfunction "GND_15") (pintype "unspecified"))
      (node (ref "U5") (pin "38") (pinfunction "GND_38") (pintype "unspecified"))
      (node (ref "U5") (pin "39") (pinfunction "GND_39") (pintype "unspecified"))
      (node (ref "U8") (pin "2") (pinfunction "SDx_2") (pintype "unspecified"))
      (node (ref "U8") (pin "3") (pinfunction "SCx_3") (pintype "unspecified"))
      (node (ref "U8") (pin "6") (pinfunction "GND_6") (pintype "unspecified"))
      (node (ref "U8") (pin "7") (pinfunction "GND_7") (pintype "unspecified"))
      (node (ref "U9") (pin "1") (pinfunction "1_1") (pintype "unspecified"))
      (node (ref "USB1") (pin "1") (pinfunction "GND_1") (pintype "unspecified"))
      (node (ref "USB1") (pin "A1B12") (pinfunction "GND_A1B12") (pintype "unspecified"))
      (node (ref "USB1") (pin "B1A12") (pinfunction "GND_B1A12") (pintype "unspecified"))
    )
    (net (code "11") (name "GPIO12") (class "Default")
      (node (ref "R1") (pin "1") (pinfunction "1_1") (pintype "input"))
      (node (ref "U5") (pin "14") (pinfunction "IO12_14") (pintype "unspecified"))
    )
    (net (code "12") (name "GPIO14") (class "Default")
      (node (ref "LED4") (pin "4") (pinfunction "DIN_4") (pintype "unspecified"))
      (node (ref "U5") (pin "13") (pinfunction "IO14_13") (pintype "unspecified"))
    )
    (net (code "13") (name "GPIO25") (class "Default")
      (node (ref "Q12") (pin "2") (pinfunction "S_2") (pintype "unspecified"))
      (node (ref "R11") (pin "1") (pinfunction "1_1") (pintype "input"))
      (node (ref "U5") (pin "10") (pinfunction "IO25_10") (pintype "unspecified"))
    )
    (net (code "14") (name "GPIO26") (class "Default")
      (node (ref "Q13") (pin "2") (pinfunction "S_2") (pintype "unspecified"))
      (node (ref "R14") (pin "1") (pinfunction "1_1") (pintype "input"))
      (node (ref "U5") (pin "11") (pinfunction "IO26_11") (pintype "unspecified"))
    )
    (net (code "15") (name "GPIO27") (class "Default")
      (node (ref "Q14") (pin "2") (pinfunction "S_2") (pintype "unspecified"))
      (node (ref "R15") (pin "1") (pinfunction "1_1") (pintype "input"))
      (node (ref "U5") (pin "12") (pinfunction "IO27_12") (pintype "unspecified"))
    )
    (net (code "16") (name "GPIO32") (class "Default")
      (node (ref "Q11") (pin "2") (pinfunction "S_2") (pintype "unspecified"))
      (node (ref "R7") (pin "1") (pinfunction "1_1") (pintype "input"))
      (node (ref "U5") (pin "8") (pinfunction "IO32_8") (pintype "unspecified"))
    )
    (net (code "17") (name "GPIO33") (class "Default")
      (node (ref "Q10") (pin "2") (pinfunction "S_2") (pintype "unspecified"))
      (node (ref "R21") (pin "1") (pinfunction "1_1") (pintype "input"))
      (node (ref "U5") (pin "9") (pinfunction "IO33_9") (pintype "unspecified"))
    )
    (net (code "18") (name "INT1") (class "Default")
      (node (ref "U5") (pin "28") (pinfunction "IO17_28") (pintype "unspecified"))
      (node (ref "U8") (pin "4") (pinfunction "INT1_4") (pintype "unspecified"))
    )
    (net (code "19") (name "INT2") (class "Default")
      (node (ref "U5") (pin "27") (pinfunction "IO16_27") (pintype "unspecified"))
      (node (ref "U8") (pin "9") (pinfunction "INT2_9") (pintype "unspecified"))
    )
    (net (code "20") (name "IO0") (class "Default")
      (node (ref "BOOT") (pin "2") (pinfunction "2_2") (pintype "unspecified"))
      (node (ref "C15") (pin "2") (pinfunction "2_2") (pintype "input"))
      (node (ref "Q3") (pin "3") (pinfunction "3_3") (pintype "input"))
      (node (ref "R20") (pin "1") (pinfunction "1_1") (pintype "input"))
      (node (ref "U5") (pin "25") (pinfunction "IO0_25") (pintype "unspecified"))
    )
    (net (code "21") (name "IO2") (class "Default")
      (node (ref "P1") (pin "2") (pinfunction "2_2") (pintype "input"))
      (node (ref "U5") (pin "24") (pinfunction "IO2_24") (pintype "unspecified"))
    )
    (net (code "22") (name "IO4") (class "Default")
      (node (ref "P1") (pin "3") (pinfunction "3_3") (pintype "input"))
      (node (ref "U5") (pin "26") (pinfunction "IO4_26") (pintype "unspecified"))
    )
    (net (code "23") (name "IO13") (class "Default")
      (node (ref "P4") (pin "1") (pinfunction "1_1") (pintype "input"))
      (node (ref "U5") (pin "16") (pinfunction "IO13_16") (pintype "unspecified"))
    )
    (net (code "24") (name "IO15") (class "Default")
      (node (ref "P1") (pin "1") (pinfunction "1_1") (pintype "input"))
      (node (ref "U5") (pin "23") (pinfunction "IO15_23") (pintype "unspecified"))
    )
    (net (code "25") (name "IO34") (class "Default")
      (node (ref "P4") (pin "3") (pinfunction "3_3") (pintype "input"))
      (node (ref "U5") (pin "6") (pinfunction "IO34_6") (pintype "unspecified"))
    )
    (net (code "26") (name "IO35") (class "Default")
      (node (ref "P4") (pin "2") (pinfunction "2_2") (pintype "input"))
      (node (ref "U5") (pin "7") (pinfunction "IO35_7") (pintype "unspecified"))
    )
    (net (code "27") (name "MISO") (class "Default")
      (node (ref "U5") (pin "31") (pinfunction "IO19_31") (pintype "unspecified"))
      (node (ref "U8") (pin "1") (pinfunction "SDO/SA0_1") (pintype "unspecified"))
    )
    (net (code "28") (name "MOSI") (class "Default")
      (node (ref "U5") (pin "37") (pinfunction "IO23_37") (pintype "unspecified"))
      (node (ref "U8") (pin "14") (pinfunction "SDA_14") (pintype "unspecified"))
    )
    (net (code "29") (name "Net-(BUZZER1--)") (class "Default")
      (node (ref "BUZZER1") (pin "2") (pinfunction "-_2") (pintype "unspecified"))
      (node (ref "D1") (pin "2") (pinfunction "A_2") (pintype "unspecified"))
      (node (ref "Q9") (pin "3") (pinfunction "C_3") (pintype "input"))
    )
    (net (code "30") (name "Net-(LED1-+)") (class "Default")
      (node (ref "LED1") (pin "2") (pinfunction "+_2") (pintype "input"))
      (node (ref "R23") (pin "2") (pinfunction "2_2") (pintype "unspecified"))
    )
    (net (code "31") (name "Net-(LED2-Pad1)") (class "Default")
      (node (ref "LED2") (pin "1") (pinfunction "1_1") (pintype "unspecified"))
      (node (ref "R18") (pin "1") (pinfunction "1_1") (pintype "unspecified"))
    )
    (net (code "32") (name "Net-(LED2-Pad2)") (class "Default")
      (node (ref "LED2") (pin "2") (pinfunction "2_2") (pintype "unspecified"))
      (node (ref "R17") (pin "1") (pinfunction "1_1") (pintype "unspecified"))
    )
    (net (code "33") (name "Net-(LED3-DIN)") (class "Default")
      (node (ref "LED3") (pin "4") (pinfunction "DIN_4") (pintype "unspecified"))
      (node (ref "LED4") (pin "2") (pinfunction "DOUT_2") (pintype "unspecified"))
    )
    (net (code "34") (name "Net-(Q2-Pad1)") (class "Default")
      (node (ref "Q2") (pin "1") (pinfunction "1_1") (pintype "input"))
      (node (ref "R2") (pin "2") (pinfunction "2_2") (pintype "input"))
    )
    (net (code "35") (name "Net-(Q9-B)") (class "Default")
      (node (ref "Q9") (pin "1") (pinfunction "B_1") (pintype "input"))
      (node (ref "R1") (pin "2") (pinfunction "2_2") (pintype "input"))
    )
    (net (code "36") (name "Net-(Q10-D)") (class "Default")
      (node (ref "Q10") (pin "3") (pinfunction "D_3") (pintype "unspecified"))
      (node (ref "R22") (pin "1") (pinfunction "1_1") (pintype "input"))
      (node (ref "U9") (pin "3") (pinfunction "3_3") (pintype "unspecified"))
    )
    (net (code "37") (name "Net-(Q11-D)") (class "Default")
      (node (ref "Q11") (pin "3") (pinfunction "D_3") (pintype "unspecified"))
      (node (ref "R8") (pin "1") (pinfunction "1_1") (pintype "input"))
      (node (ref "U10") (pin "3") (pinfunction "3_3") (pintype "unspecified"))
    )
    (net (code "38") (name "Net-(Q12-D)") (class "Default")
      (node (ref "Q12") (pin "3") (pinfunction "D_3") (pintype "unspecified"))
      (node (ref "R12") (pin "1") (pinfunction "1_1") (pintype "input"))
      (node (ref "U11") (pin "3") (pinfunction "3_3") (pintype "unspecified"))
    )
    (net (code "39") (name "Net-(Q13-D)") (class "Default")
      (node (ref "Q13") (pin "3") (pinfunction "D_3") (pintype "unspecified"))
      (node (ref "R13") (pin "1") (pinfunction "1_1") (pintype "input"))
      (node (ref "U12") (pin "3") (pinfunction "3_3") (pintype "unspecified"))
    )
    (net (code "40") (name "Net-(Q14-D)") (class "Default")
      (node (ref "Q14") (pin "3") (pinfunction "D_3") (pintype "unspecified"))
      (node (ref "R16") (pin "1") (pinfunction "1_1") (pintype "input"))
      (node (ref "U13") (pin "3") (pinfunction "3_3") (pintype "unspecified"))
    )
    (net (code "41") (name "RTS") (class "Default")
      (node (ref "Q2") (pin "2") (pinfunction "2_2") (pintype "input"))
      (node (ref "Q3") (pin "1") (pinfunction "1_1") (pintype "input"))
      (node (ref "U2") (pin "14") (pinfunction "RTS#_14") (pintype "unspecified"))
    )
    (net (code "42") (name "RXD") (class "Default")
      (node (ref "LED2") (pin "4") (pinfunction "4_4") (pintype "unspecified"))
      (node (ref "U16") (pin "3") (pinfunction "3_3") (pintype "unspecified"))
      (node (ref "U2") (pin "3") (pinfunction "RXD_3") (pintype "unspecified"))
      (node (ref "U5") (pin "35") (pinfunction "TXD0_35") (pintype "unspecified"))
    )
    (net (code "43") (name "SCK") (class "Default")
      (node (ref "U5") (pin "30") (pinfunction "IO18_30") (pintype "unspecified"))
      (node (ref "U8") (pin "13") (pinfunction "SCL_13") (pintype "unspecified"))
    )
    (net (code "44") (name "SCL") (class "Default")
      (node (ref "U15") (pin "3") (pinfunction "3_3") (pintype "unspecified"))
      (node (ref "U5") (pin "36") (pinfunction "IO22_36") (pintype "unspecified"))
    )
    (net (code "45") (name "SDA") (class "Default")
      (node (ref "U15") (pin "2") (pinfunction "2_2") (pintype "unspecified"))
      (node (ref "U5") (pin "33") (pinfunction "IO21_33") (pintype "unspecified"))
    )
    (net (code "46") (name "TXD") (class "Default")
      (node (ref "LED2") (pin "3") (pinfunction "3_3") (pintype "unspecified"))
      (node (ref "U16") (pin "2") (pinfunction "2_2") (pintype "unspecified"))
      (node (ref "U2") (pin "2") (pinfunction "TXD_2") (pintype "unspecified"))
      (node (ref "U5") (pin "34") (pinfunction "RXD0_34") (pintype "unspecified"))
    )
    (net (code "47") (name "VIN") (class "Default")
      (node (ref "CN1") (pin "1") (pinfunction "1_1") (pintype "unspecified"))
      (node (ref "Q1") (pin "3") (pinfunction "D_3") (pintype "unspecified"))
    )
    (net (code "48") (name "unconnected-(BOOT-Pad3)") (class "Default")
      (node (ref "BOOT") (pin "3") (pinfunction "3_3") (pintype "unspecified+no_connect"))
    )
    (net (code "49") (name "unconnected-(BOOT-Pad4)") (class "Default")
      (node (ref "BOOT") (pin "4") (pinfunction "4_4") (pintype "unspecified+no_connect"))
    )
    (net (code "50") (name "unconnected-(BUZZER1-Pad3)") (class "Default")
      (node (ref "BUZZER1") (pin "3") (pinfunction "3_3") (pintype "unspecified+no_connect"))
    )
    (net (code "51") (name "unconnected-(BUZZER1-Pad4)") (class "Default")
      (node (ref "BUZZER1") (pin "4") (pinfunction "4_4") (pintype "unspecified+no_connect"))
    )
    (net (code "52") (name "unconnected-(EN-Pad3)") (class "Default")
      (node (ref "EN") (pin "3") (pinfunction "3_3") (pintype "unspecified+no_connect"))
    )
    (net (code "53") (name "unconnected-(EN-Pad4)") (class "Default")
      (node (ref "EN") (pin "4") (pinfunction "4_4") (pintype "unspecified+no_connect"))
    )
    (net (code "54") (name "unconnected-(LED3-DOUT-Pad2)") (class "Default")
      (node (ref "LED3") (pin "2") (pinfunction "DOUT_2") (pintype "unspecified+no_connect"))
    )
    (net (code "55") (name "unconnected-(U1-VOUT(TAB)-Pad2)") (class "Default")
      (node (ref "U1") (pin "2") (pinfunction "VOUT(TAB)_2") (pintype "unspecified+no_connect"))
    )
    (net (code "56") (name "unconnected-(U2-CTS#-Pad9)") (class "Default")
      (node (ref "U2") (pin "9") (pinfunction "CTS#_9") (pintype "unspecified+no_connect"))
    )
    (net (code "57") (name "unconnected-(U2-DCD#-Pad12)") (class "Default")
      (node (ref "U2") (pin "12") (pinfunction "DCD#_12") (pintype "unspecified+no_connect"))
    )
    (net (code "58") (name "unconnected-(U2-DSR#-Pad10)") (class "Default")
      (node (ref "U2") (pin "10") (pinfunction "DSR#_10") (pintype "unspecified+no_connect"))
    )
    (net (code "59") (name "unconnected-(U2-NC.-Pad7)") (class "Default")
      (node (ref "U2") (pin "7") (pinfunction "NC._7") (pintype "unspecified+no_connect"))
    )
    (net (code "60") (name "unconnected-(U2-NC.-Pad8)") (class "Default")
      (node (ref "U2") (pin "8") (pinfunction "NC._8") (pintype "unspecified+no_connect"))
    )
    (net (code "61") (name "unconnected-(U2-R232-Pad15)") (class "Default")
      (node (ref "U2") (pin "15") (pinfunction "R232_15") (pintype "unspecified+no_connect"))
    )
    (net (code "62") (name "unconnected-(U2-RI#-Pad11)") (class "Default")
      (node (ref "U2") (pin "11") (pinfunction "RI#_11") (pintype "unspecified+no_connect"))
    )
    (net (code "63") (name "unconnected-(U5-NC-Pad17)") (class "Default")
      (node (ref "U5") (pin "17") (pinfunction "NC_17") (pintype "unspecified+no_connect"))
    )
    (net (code "64") (name "unconnected-(U5-NC-Pad18)") (class "Default")
      (node (ref "U5") (pin "18") (pinfunction "NC_18") (pintype "unspecified+no_connect"))
    )
    (net (code "65") (name "unconnected-(U5-NC-Pad19)") (class "Default")
      (node (ref "U5") (pin "19") (pinfunction "NC_19") (pintype "unspecified+no_connect"))
    )
    (net (code "66") (name "unconnected-(U5-NC-Pad20)") (class "Default")
      (node (ref "U5") (pin "20") (pinfunction "NC_20") (pintype "unspecified+no_connect"))
    )
    (net (code "67") (name "unconnected-(U5-NC-Pad21)") (class "Default")
      (node (ref "U5") (pin "21") (pinfunction "NC_21") (pintype "unspecified+no_connect"))
    )
    (net (code "68") (name "unconnected-(U5-NC-Pad22)") (class "Default")
      (node (ref "U5") (pin "22") (pinfunction "NC_22") (pintype "unspecified+no_connect"))
    )
    (net (code "69") (name "unconnected-(U5-NC-Pad32)") (class "Default")
      (node (ref "U5") (pin "32") (pinfunction "NC_32") (pintype "unspecified+no_connect"))
    )
    (net (code "70") (name "unconnected-(U5-SENSOR_VN-Pad5)") (class "Default")
      (node (ref "U5") (pin "5") (pinfunction "SENSOR_VN_5") (pintype "unspecified+no_connect"))
    )
    (net (code "71") (name "unconnected-(U5-SENSOR_VP-Pad4)") (class "Default")
      (node (ref "U5") (pin "4") (pinfunction "SENSOR_VP_4") (pintype "unspecified+no_connect"))
    )
    (net (code "72") (name "unconnected-(U8-NC-Pad10)") (class "Default")
      (node (ref "U8") (pin "10") (pinfunction "NC_10") (pintype "unspecified+no_connect"))
    )
    (net (code "73") (name "unconnected-(U8-NC-Pad11)") (class "Default")
      (node (ref "U8") (pin "11") (pinfunction "NC_11") (pintype "unspecified+no_connect"))
    )
    (net (code "74") (name "unconnected-(USB1-SBU1-PadA8)") (class "Default")
      (node (ref "USB1") (pin "A8") (pinfunction "SBU1_A8") (pintype "unspecified+no_connect"))
    )
    (net (code "75") (name "unconnected-(USB1-SBU2-PadB8)") (class "Default")
      (node (ref "USB1") (pin "B8") (pinfunction "SBU2_B8") (pintype "unspecified+no_connect"))
    )
  )
)
